# Mainboard_v4.net
KiCad netlist of a schematic drawn in EAGLE
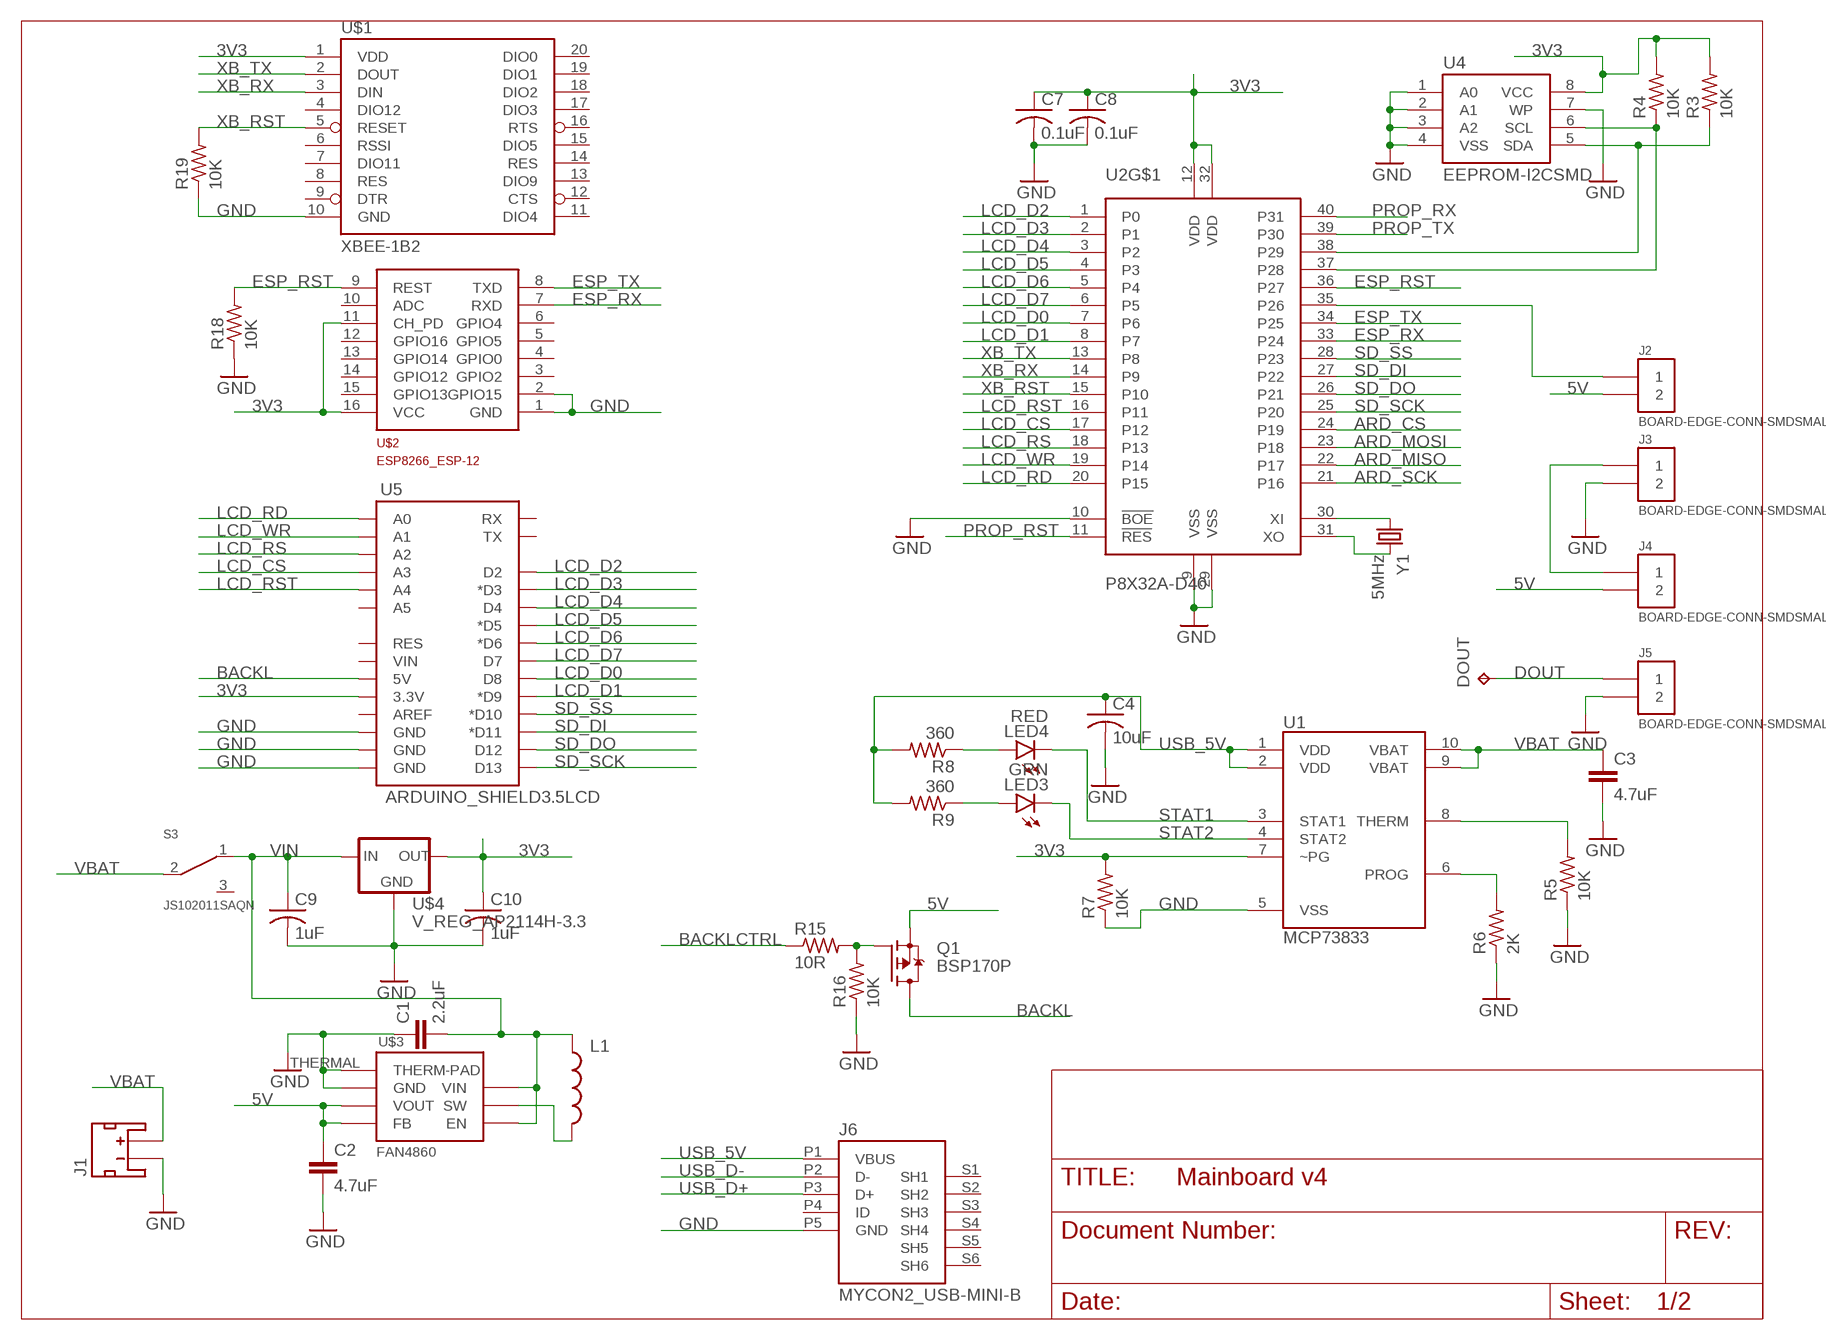
[diagram p0: schematic, sheet 1]
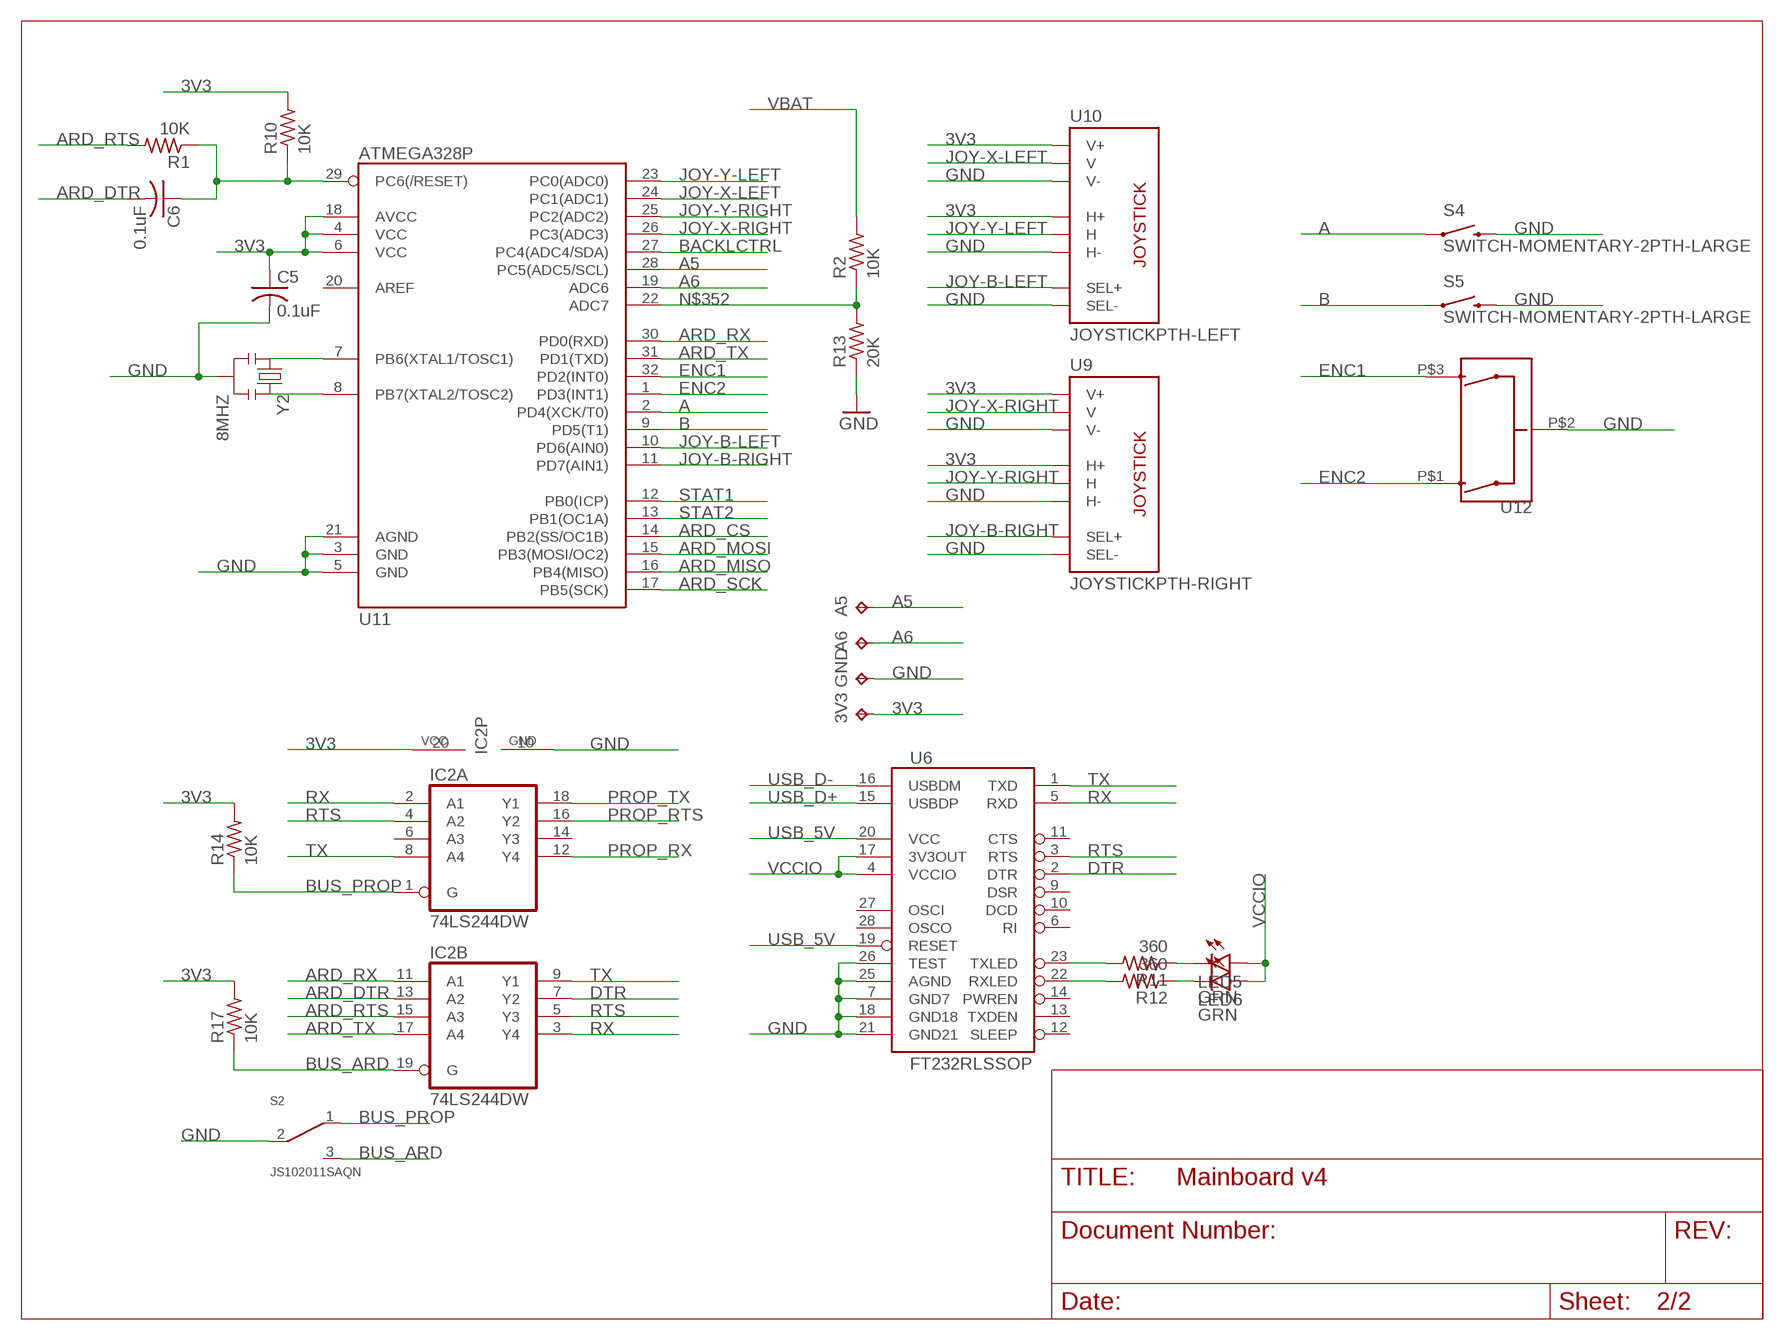
[diagram p1: schematic, sheet 2]

(export (version "E")
  (design (tool "Eeschema 10.0.6"))
  (components
    (comp (ref "C1")
      (value "2.2uF")
      (footprint "eagle-import:0402-CAP")
      (libsource (lib "eagle-import") (part "CAP0402-CAP"))
    )
    (comp (ref "C2")
      (value "4.7uF")
      (footprint "eagle-import:0603-CAP")
      (libsource (lib "eagle-import") (part "CAP0603-CAP"))
    )
    (comp (ref "C3")
      (value "4.7uF")
      (footprint "eagle-import:0603-CAP")
      (libsource (lib "eagle-import") (part "CAP0603-CAP"))
    )
    (comp (ref "C4")
      (value "10uF")
      (footprint "eagle-import:C1206K")
      (libsource (lib "eagle-import") (part "C-USC1206K"))
    )
    (comp (ref "C7")
      (value "0.1uF")
      (footprint "eagle-import:C0805")
      (libsource (lib "eagle-import") (part "C-USC0805"))
    )
    (comp (ref "C8")
      (value "0.1uF")
      (footprint "eagle-import:C0805")
      (libsource (lib "eagle-import") (part "C-USC0805"))
    )
    (comp (ref "C9")
      (value "1uF")
      (footprint "eagle-import:C1206K")
      (libsource (lib "eagle-import") (part "C-USC1206K"))
    )
    (comp (ref "C10")
      (value "1uF")
      (footprint "eagle-import:C1206K")
      (libsource (lib "eagle-import") (part "C-USC1206K"))
    )
    (comp (ref "DOUT")
      (value "TPPAD1-13")
      (footprint "eagle-import:P1-13")
      (libsource (lib "eagle-import") (part "TPPAD1-13"))
    )
    (comp (ref "J1")
      (value "JST_2MM_MALE")
      (footprint "eagle-import:JST-2-SMD")
      (libsource (lib "eagle-import") (part "JST_2MM_MALE"))
    )
    (comp (ref "J2")
      (value "BOARD-EDGE-CONN-SMDSMALL")
      (footprint "eagle-import:SMD-2-SMALL")
      (libsource (lib "eagle-import") (part "BOARD-EDGE-CONN-SMDSMALL"))
    )
    (comp (ref "J3")
      (value "BOARD-EDGE-CONN-SMDSMALL")
      (footprint "eagle-import:SMD-2-SMALL")
      (libsource (lib "eagle-import") (part "BOARD-EDGE-CONN-SMDSMALL"))
    )
    (comp (ref "J4")
      (value "BOARD-EDGE-CONN-SMDSMALL")
      (footprint "eagle-import:SMD-2-SMALL")
      (libsource (lib "eagle-import") (part "BOARD-EDGE-CONN-SMDSMALL"))
    )
    (comp (ref "J5")
      (value "BOARD-EDGE-CONN-SMDSMALL")
      (footprint "eagle-import:SMD-2-SMALL")
      (libsource (lib "eagle-import") (part "BOARD-EDGE-CONN-SMDSMALL"))
    )
    (comp (ref "J6")
      (value "MYCON2_USB-MINI-B")
      (footprint "eagle-import:CON2_USB_MICRO_B_AT")
      (libsource (lib "eagle-import") (part "MYCON2_USB-MINI-B"))
    )
    (comp (ref "L1")
      (value "INDUCTOR0805")
      (footprint "eagle-import:0805")
      (libsource (lib "eagle-import") (part "INDUCTOR0805"))
    )
    (comp (ref "LED3")
      (value "GRN")
      (footprint "eagle-import:LED-0603")
      (libsource (lib "eagle-import") (part "LED0603"))
    )
    (comp (ref "LED4")
      (value "RED")
      (footprint "eagle-import:LED-0603")
      (libsource (lib "eagle-import") (part "LED0603"))
    )
    (comp (ref "Q1")
      (value "BSP170P")
      (footprint "eagle-import:SOT223")
      (libsource (lib "eagle-import") (part "BSP170P"))
    )
    (comp (ref "R3")
      (value "10K")
      (footprint "eagle-import:R0603")
      (libsource (lib "eagle-import") (part "R-US_R0603"))
    )
    (comp (ref "R4")
      (value "10K")
      (footprint "eagle-import:R0603")
      (libsource (lib "eagle-import") (part "R-US_R0603"))
    )
    (comp (ref "R5")
      (value "10K")
      (footprint "eagle-import:R0603")
      (libsource (lib "eagle-import") (part "R-US_R0603"))
    )
    (comp (ref "R6")
      (value "2K")
      (footprint "eagle-import:R0603")
      (libsource (lib "eagle-import") (part "R-US_R0603"))
    )
    (comp (ref "R7")
      (value "10K")
      (footprint "eagle-import:R0603")
      (libsource (lib "eagle-import") (part "R-US_R0603"))
    )
    (comp (ref "R8")
      (value "360")
      (footprint "eagle-import:R0603")
      (libsource (lib "eagle-import") (part "R-US_R0603"))
    )
    (comp (ref "R9")
      (value "360")
      (footprint "eagle-import:R0603")
      (libsource (lib "eagle-import") (part "R-US_R0603"))
    )
    (comp (ref "R15")
      (value "10R")
      (footprint "eagle-import:R0603")
      (libsource (lib "eagle-import") (part "R-US_R0603"))
    )
    (comp (ref "R16")
      (value "10K")
      (footprint "eagle-import:R0603")
      (libsource (lib "eagle-import") (part "R-US_R0603"))
    )
    (comp (ref "R18")
      (value "10K")
      (footprint "eagle-import:R0603")
      (libsource (lib "eagle-import") (part "R-US_R0603"))
    )
    (comp (ref "R19")
      (value "10K")
      (footprint "eagle-import:R0603")
      (libsource (lib "eagle-import") (part "R-US_R0603"))
    )
    (comp (ref "S3")
      (value "JS102011SAQN")
      (footprint "eagle-import:SAQN")
      (libsource (lib "eagle-import") (part "JS102011SAQN"))
    )
    (comp (ref "U$1")
      (value "XBEE-1B2")
      (footprint "eagle-import:XBEE-SILK")
      (libsource (lib "eagle-import") (part "XBEE-1B2"))
    )
    (comp (ref "U$2")
      (value "ESP8266_ESP-12")
      (footprint "eagle-import:ESP8266-ESP12E")
      (libsource (lib "eagle-import") (part "ESP8266_ESP-12"))
    )
    (comp (ref "U$3")
      (value "FAN4860")
      (footprint "eagle-import:6-UMLP")
      (libsource (lib "eagle-import") (part "FAN4860"))
    )
    (comp (ref "U$4")
      (value "V_REG_AP2114H-3.3")
      (footprint "eagle-import:SOT223")
      (libsource (lib "eagle-import") (part "V_REG_MIC2920AP2114"))
    )
    (comp (ref "U1")
      (value "MCP73833")
      (footprint "eagle-import:MSOP-10")
      (libsource (lib "eagle-import") (part "MCP73833"))
    )
    (comp (ref "U2")
      (value "P8X32A-D40")
      (footprint "eagle-import:DIP-40")
      (libsource (lib "eagle-import") (part "P8X32A-D40"))
    )
    (comp (ref "U4")
      (value "EEPROM-I2CSMD")
      (footprint "eagle-import:SO08")
      (libsource (lib "eagle-import") (part "EEPROM-I2CSMD"))
    )
    (comp (ref "U5")
      (value "ARDUINO_SHIELD3.5LCD")
      (footprint "eagle-import:3.6TFT-LCD-SHIELD")
      (libsource (lib "eagle-import") (part "ARDUINO_SHIELD3.5LCD"))
    )
    (comp (ref "Y1")
      (value "5MHz")
      (footprint "eagle-import:CRYSTAL-SMD")
      (libsource (lib "eagle-import") (part "CRYSTAL-TH-11.5X5MM"))
    )
    (comp (ref "3V3")
      (value "TPPAD1-13")
      (footprint "eagle-import:P1-13")
      (libsource (lib "eagle-import") (part "TPPAD1-13"))
    )
    (comp (ref "A5")
      (value "TPPAD1-13")
      (footprint "eagle-import:P1-13")
      (libsource (lib "eagle-import") (part "TPPAD1-13"))
    )
    (comp (ref "A6")
      (value "TPPAD1-13")
      (footprint "eagle-import:P1-13")
      (libsource (lib "eagle-import") (part "TPPAD1-13"))
    )
    (comp (ref "C5")
      (value "0.1uF")
      (footprint "eagle-import:C0805")
      (libsource (lib "eagle-import") (part "C-USC0805"))
    )
    (comp (ref "C6")
      (value "0.1uF")
      (footprint "eagle-import:C0805")
      (libsource (lib "eagle-import") (part "C-USC0805"))
    )
    (comp (ref "GND")
      (value "TPPAD1-13")
      (footprint "eagle-import:P1-13")
      (libsource (lib "eagle-import") (part "TPPAD1-13"))
    )
    (comp (ref "IC2")
      (value "74LS244DW")
      (footprint "eagle-import:SO20W")
      (libsource (lib "eagle-import") (part "74244DWLS"))
    )
    (comp (ref "LED5")
      (value "GRN")
      (footprint "eagle-import:LED-0603")
      (libsource (lib "eagle-import") (part "LED0603"))
    )
    (comp (ref "LED6")
      (value "GRN")
      (footprint "eagle-import:LED-0603")
      (libsource (lib "eagle-import") (part "LED0603"))
    )
    (comp (ref "R1")
      (value "10K")
      (footprint "eagle-import:R0603")
      (libsource (lib "eagle-import") (part "R-US_R0603"))
    )
    (comp (ref "R2")
      (value "10K")
      (footprint "eagle-import:R0603")
      (libsource (lib "eagle-import") (part "R-US_R0603"))
    )
    (comp (ref "R10")
      (value "10K")
      (footprint "eagle-import:R0603")
      (libsource (lib "eagle-import") (part "R-US_R0603"))
    )
    (comp (ref "R11")
      (value "360")
      (footprint "eagle-import:R0603")
      (libsource (lib "eagle-import") (part "R-US_R0603"))
    )
    (comp (ref "R12")
      (value "360")
      (footprint "eagle-import:R0603")
      (libsource (lib "eagle-import") (part "R-US_R0603"))
    )
    (comp (ref "R13")
      (value "20K")
      (footprint "eagle-import:R0603")
      (libsource (lib "eagle-import") (part "R-US_R0603"))
    )
    (comp (ref "R14")
      (value "10K")
      (footprint "eagle-import:R0603")
      (libsource (lib "eagle-import") (part "R-US_R0603"))
    )
    (comp (ref "R17")
      (value "10K")
      (footprint "eagle-import:R0603")
      (libsource (lib "eagle-import") (part "R-US_R0603"))
    )
    (comp (ref "S2")
      (value "JS102011SAQN")
      (footprint "eagle-import:SAQN")
      (libsource (lib "eagle-import") (part "JS102011SAQN"))
    )
    (comp (ref "S4")
      (value "SWITCH-MOMENTARY-2PTH-LARGE")
      (footprint "eagle-import:TACTILE-PTH-LARGE")
      (libsource (lib "eagle-import") (part "SWITCH-MOMENTARY-2PTH-LARGE"))
    )
    (comp (ref "S5")
      (value "SWITCH-MOMENTARY-2PTH-LARGE")
      (footprint "eagle-import:TACTILE-PTH-LARGE")
      (libsource (lib "eagle-import") (part "SWITCH-MOMENTARY-2PTH-LARGE"))
    )
    (comp (ref "U6")
      (value "FT232RLSSOP")
      (footprint "eagle-import:SSOP28DB")
      (libsource (lib "eagle-import") (part "FT232RLSSOP"))
    )
    (comp (ref "U9")
      (value "JOYSTICKPTH-RIGHT")
      (footprint "eagle-import:JOYSTICK")
      (libsource (lib "eagle-import") (part "JOYSTICKPTH"))
    )
    (comp (ref "U10")
      (value "JOYSTICKPTH-LEFT")
      (footprint "eagle-import:JOYSTICK")
      (libsource (lib "eagle-import") (part "JOYSTICKPTH"))
    )
    (comp (ref "U11")
      (value "ATMEGA328P")
      (footprint "eagle-import:TQFP32-08")
      (libsource (lib "eagle-import") (part "ATMEGA328_SMT"))
    )
    (comp (ref "U12")
      (value "ENCODER-QUADRATURE")
      (footprint "eagle-import:ENCODER-12MM-VERT-SQ")
      (libsource (lib "eagle-import") (part "ENCODER-QUADRATURE"))
    )
    (comp (ref "Y2")
      (value "8MHZ")
      (footprint "eagle-import:RESONATOR-AWSCR-CV")
      (libsource (lib "eagle-import") (part "RESONATORAWSCR"))
    )
  )
  (nets
    (net (code "1") (name "3V3") (class "Default")
      (node (ref "3V3") (pin "TP") (pinfunction "TP_TP") (pintype "input"))
      (node (ref "C10") (pin "1") (pinfunction "1_1") (pintype "passive"))
      (node (ref "C5") (pin "1") (pinfunction "1_1") (pintype "passive"))
      (node (ref "C7") (pin "1") (pinfunction "1_1") (pintype "passive"))
      (node (ref "C8") (pin "1") (pinfunction "1_1") (pintype "passive"))
      (node (ref "IC2") (pin "20") (pinfunction "VCC_20") (pintype "power_in"))
      (node (ref "R10") (pin "2") (pinfunction "2_2") (pintype "passive"))
      (node (ref "R14") (pin "2") (pinfunction "2_2") (pintype "passive"))
      (node (ref "R17") (pin "2") (pinfunction "2_2") (pintype "passive"))
      (node (ref "R3") (pin "2") (pinfunction "2_2") (pintype "passive"))
      (node (ref "R4") (pin "2") (pinfunction "2_2") (pintype "passive"))
      (node (ref "R7") (pin "2") (pinfunction "2_2") (pintype "passive"))
      (node (ref "U$1") (pin "1") (pinfunction "VDD_1") (pintype "power_in"))
      (node (ref "U$2") (pin "11") (pinfunction "CH_PD_11") (pintype "bidirectional"))
      (node (ref "U$2") (pin "16") (pinfunction "VCC_16") (pintype "bidirectional"))
      (node (ref "U$4") (pin "2") (pinfunction "OUT_2") (pintype "output"))
      (node (ref "U1") (pin "7") (pinfunction "~{PG}_7") (pintype "bidirectional"))
      (node (ref "U10") (pin "H1") (pinfunction "H+_H1") (pintype "bidirectional"))
      (node (ref "U10") (pin "V1") (pinfunction "V+_V1") (pintype "bidirectional"))
      (node (ref "U11") (pin "18") (pinfunction "AVCC_18") (pintype "bidirectional"))
      (node (ref "U11") (pin "4") (pinfunction "VCC_4") (pintype "bidirectional"))
      (node (ref "U11") (pin "6") (pinfunction "VCC_6") (pintype "bidirectional"))
      (node (ref "U2") (pin "12") (pinfunction "VDD_12") (pintype "input"))
      (node (ref "U2") (pin "32") (pinfunction "VDD_32") (pintype "input"))
      (node (ref "U4") (pin "8") (pinfunction "VCC_8") (pintype "power_in"))
      (node (ref "U5") (pin "3.3V") (pinfunction "3.3V_3.3V") (pintype "bidirectional"))
      (node (ref "U9") (pin "H1") (pinfunction "H+_H1") (pintype "bidirectional"))
      (node (ref "U9") (pin "V1") (pinfunction "V+_V1") (pintype "bidirectional"))
    )
    (net (code "2") (name "5V") (class "Default")
      (node (ref "C2") (pin "1") (pinfunction "1_1") (pintype "passive"))
      (node (ref "J2") (pin "P$2") (pinfunction "2_P$2") (pintype "bidirectional"))
      (node (ref "J4") (pin "P$2") (pinfunction "2_P$2") (pintype "bidirectional"))
      (node (ref "Q1") (pin "3") (pinfunction "S_3") (pintype "passive"))
      (node (ref "U$3") (pin "P$2") (pinfunction "VOUT_P$2") (pintype "bidirectional"))
      (node (ref "U$3") (pin "P$3") (pinfunction "FB_P$3") (pintype "bidirectional"))
    )
    (net (code "3") (name "A") (class "Default")
      (node (ref "S4") (pin "P$1") (pinfunction "1_P$1") (pintype "passive"))
      (node (ref "U11") (pin "2") (pinfunction "PD4(XCK/T0)_2") (pintype "bidirectional"))
    )
    (net (code "4") (name "A5") (class "Default")
      (node (ref "A5") (pin "TP") (pinfunction "TP_TP") (pintype "input"))
      (node (ref "U11") (pin "28") (pinfunction "PC5(ADC5/SCL)_28") (pintype "bidirectional"))
    )
    (net (code "5") (name "A6") (class "Default")
      (node (ref "A6") (pin "TP") (pinfunction "TP_TP") (pintype "input"))
      (node (ref "U11") (pin "19") (pinfunction "ADC6_19") (pintype "bidirectional"))
    )
    (net (code "6") (name "ARD_CS") (class "Default")
      (node (ref "U11") (pin "14") (pinfunction "PB2(SS/OC1B)_14") (pintype "bidirectional"))
      (node (ref "U2") (pin "24") (pinfunction "P19_24") (pintype "bidirectional"))
    )
    (net (code "7") (name "ARD_DTR") (class "Default")
      (node (ref "C6") (pin "2") (pinfunction "2_2") (pintype "passive"))
      (node (ref "IC2") (pin "13") (pinfunction "A2_13") (pintype "input"))
    )
    (net (code "8") (name "ARD_MISO") (class "Default")
      (node (ref "U11") (pin "16") (pinfunction "PB4(MISO)_16") (pintype "bidirectional"))
      (node (ref "U2") (pin "22") (pinfunction "P17_22") (pintype "bidirectional"))
    )
    (net (code "9") (name "ARD_MOSI") (class "Default")
      (node (ref "U11") (pin "15") (pinfunction "PB3(MOSI/OC2)_15") (pintype "bidirectional"))
      (node (ref "U2") (pin "23") (pinfunction "P18_23") (pintype "bidirectional"))
    )
    (net (code "10") (name "ARD_RTS") (class "Default")
      (node (ref "IC2") (pin "15") (pinfunction "A3_15") (pintype "input"))
      (node (ref "R1") (pin "2") (pinfunction "2_2") (pintype "passive"))
    )
    (net (code "11") (name "ARD_RX") (class "Default")
      (node (ref "IC2") (pin "11") (pinfunction "A1_11") (pintype "input"))
      (node (ref "U11") (pin "30") (pinfunction "PD0(RXD)_30") (pintype "bidirectional"))
    )
    (net (code "12") (name "ARD_SCK") (class "Default")
      (node (ref "U11") (pin "17") (pinfunction "PB5(SCK)_17") (pintype "bidirectional"))
      (node (ref "U2") (pin "21") (pinfunction "P16_21") (pintype "bidirectional"))
    )
    (net (code "13") (name "ARD_TX") (class "Default")
      (node (ref "IC2") (pin "17") (pinfunction "A4_17") (pintype "input"))
      (node (ref "U11") (pin "31") (pinfunction "PD1(TXD)_31") (pintype "bidirectional"))
    )
    (net (code "14") (name "B") (class "Default")
      (node (ref "S5") (pin "P$1") (pinfunction "1_P$1") (pintype "passive"))
      (node (ref "U11") (pin "9") (pinfunction "PD5(T1)_9") (pintype "bidirectional"))
    )
    (net (code "15") (name "BACKL") (class "Default")
      (node (ref "Q1") (pin "2") (pinfunction "D_2") (pintype "passive"))
      (node (ref "Q1") (pin "4") (pinfunction "D_4") (pintype "passive"))
      (node (ref "U5") (pin "5V") (pinfunction "5V_5V") (pintype "bidirectional"))
    )
    (net (code "16") (name "BACKLCTRL") (class "Default")
      (node (ref "R15") (pin "1") (pinfunction "1_1") (pintype "passive"))
      (node (ref "U11") (pin "27") (pinfunction "PC4(ADC4/SDA)_27") (pintype "bidirectional"))
    )
    (net (code "17") (name "BUS_ARD") (class "Default")
      (node (ref "IC2") (pin "19") (pinfunction "G_19") (pintype "input"))
      (node (ref "R17") (pin "1") (pinfunction "1_1") (pintype "passive"))
      (node (ref "S2") (pin "3") (pinfunction "P3_3") (pintype "bidirectional"))
    )
    (net (code "18") (name "BUS_PROP") (class "Default")
      (node (ref "IC2") (pin "1") (pinfunction "G_1") (pintype "input"))
      (node (ref "R14") (pin "1") (pinfunction "1_1") (pintype "passive"))
      (node (ref "S2") (pin "1") (pinfunction "P1_1") (pintype "bidirectional"))
    )
    (net (code "19") (name "DOUT") (class "Default")
      (node (ref "DOUT") (pin "TP") (pinfunction "TP_TP") (pintype "input"))
      (node (ref "J5") (pin "P$1") (pinfunction "1_P$1") (pintype "bidirectional"))
    )
    (net (code "20") (name "DTR") (class "Default")
      (node (ref "IC2") (pin "7") (pinfunction "Y2_7") (pintype "tri_state"))
      (node (ref "U6") (pin "2") (pinfunction "DTR_2") (pintype "output"))
    )
    (net (code "21") (name "ENC1") (class "Default")
      (node (ref "U11") (pin "32") (pinfunction "PD2(INT0)_32") (pintype "bidirectional"))
      (node (ref "U12") (pin "P$3") (pinfunction "B_P$3") (pintype "bidirectional"))
    )
    (net (code "22") (name "ENC2") (class "Default")
      (node (ref "U11") (pin "1") (pinfunction "PD3(INT1)_1") (pintype "bidirectional"))
      (node (ref "U12") (pin "P$1") (pinfunction "A_P$1") (pintype "bidirectional"))
    )
    (net (code "23") (name "ESP_RST") (class "Default")
      (node (ref "R18") (pin "2") (pinfunction "2_2") (pintype "passive"))
      (node (ref "U$2") (pin "9") (pinfunction "REST_9") (pintype "bidirectional"))
      (node (ref "U2") (pin "36") (pinfunction "P27_36") (pintype "bidirectional"))
    )
    (net (code "24") (name "ESP_RX") (class "Default")
      (node (ref "U$2") (pin "7") (pinfunction "RXD_7") (pintype "bidirectional"))
      (node (ref "U2") (pin "33") (pinfunction "P24_33") (pintype "bidirectional"))
    )
    (net (code "25") (name "ESP_TX") (class "Default")
      (node (ref "U$2") (pin "8") (pinfunction "TXD_8") (pintype "bidirectional"))
      (node (ref "U2") (pin "34") (pinfunction "P25_34") (pintype "bidirectional"))
    )
    (net (code "26") (name "GND") (class "Default")
      (node (ref "C1") (pin "1") (pinfunction "1_1") (pintype "passive"))
      (node (ref "C10") (pin "2") (pinfunction "2_2") (pintype "passive"))
      (node (ref "C2") (pin "2") (pinfunction "2_2") (pintype "passive"))
      (node (ref "C3") (pin "2") (pinfunction "2_2") (pintype "passive"))
      (node (ref "C4") (pin "2") (pinfunction "2_2") (pintype "passive"))
      (node (ref "C5") (pin "2") (pinfunction "2_2") (pintype "passive"))
      (node (ref "C7") (pin "2") (pinfunction "2_2") (pintype "passive"))
      (node (ref "C8") (pin "2") (pinfunction "2_2") (pintype "passive"))
      (node (ref "C9") (pin "2") (pinfunction "2_2") (pintype "passive"))
      (node (ref "GND") (pin "TP") (pinfunction "TP_TP") (pintype "input"))
      (node (ref "IC2") (pin "10") (pinfunction "GND_10") (pintype "power_in"))
      (node (ref "J1") (pin "1") (pinfunction "-_1") (pintype "bidirectional"))
      (node (ref "J3") (pin "P$2") (pinfunction "2_P$2") (pintype "bidirectional"))
      (node (ref "J5") (pin "P$2") (pinfunction "2_P$2") (pintype "bidirectional"))
      (node (ref "J6") (pin "P5") (pinfunction "GND_P5") (pintype "passive"))
      (node (ref "R13") (pin "1") (pinfunction "1_1") (pintype "passive"))
      (node (ref "R16") (pin "1") (pinfunction "1_1") (pintype "passive"))
      (node (ref "R18") (pin "1") (pinfunction "1_1") (pintype "passive"))
      (node (ref "R19") (pin "1") (pinfunction "1_1") (pintype "passive"))
      (node (ref "R5") (pin "1") (pinfunction "1_1") (pintype "passive"))
      (node (ref "R6") (pin "1") (pinfunction "1_1") (pintype "passive"))
      (node (ref "R7") (pin "1") (pinfunction "1_1") (pintype "passive"))
      (node (ref "S2") (pin "2") (pinfunction "P2_2") (pintype "bidirectional"))
      (node (ref "S4") (pin "P$2") (pinfunction "2_P$2") (pintype "passive"))
      (node (ref "S5") (pin "P$2") (pinfunction "2_P$2") (pintype "passive"))
      (node (ref "U$1") (pin "10") (pinfunction "GND_10") (pintype "power_in"))
      (node (ref "U$2") (pin "1") (pinfunction "GND_1") (pintype "bidirectional"))
      (node (ref "U$2") (pin "2") (pinfunction "GPIO15_2") (pintype "bidirectional"))
      (node (ref "U$3") (pin "P$1") (pinfunction "GND_P$1") (pintype "bidirectional"))
      (node (ref "U$3") (pin "THERMAL") (pinfunction "THERM-PAD_THERMAL") (pintype "bidirectional"))
      (node (ref "U$4") (pin "1") (pinfunction "GND_1") (pintype "input"))
      (node (ref "U1") (pin "5") (pinfunction "VSS_5") (pintype "bidirectional"))
      (node (ref "U10") (pin "B2A") (pinfunction "SEL-_B2A") (pintype "bidirectional"))
      (node (ref "U10") (pin "H3") (pinfunction "H-_H3") (pintype "bidirectional"))
      (node (ref "U10") (pin "V3") (pinfunction "V-_V3") (pintype "bidirectional"))
      (node (ref "U11") (pin "21") (pinfunction "AGND_21") (pintype "bidirectional"))
      (node (ref "U11") (pin "3") (pinfunction "GND_3") (pintype "bidirectional"))
      (node (ref "U11") (pin "5") (pinfunction "GND_5") (pintype "bidirectional"))
      (node (ref "U12") (pin "P$2") (pinfunction "C_P$2") (pintype "bidirectional"))
      (node (ref "U2") (pin "10") (pinfunction "~{BOE}_10") (pintype "input"))
      (node (ref "U2") (pin "29") (pinfunction "VSS_29") (pintype "input"))
      (node (ref "U2") (pin "9") (pinfunction "VSS_9") (pintype "input"))
      (node (ref "U4") (pin "1") (pinfunction "A0_1") (pintype "bidirectional"))
      (node (ref "U4") (pin "2") (pinfunction "A1_2") (pintype "bidirectional"))
      (node (ref "U4") (pin "3") (pinfunction "A2_3") (pintype "bidirectional"))
      (node (ref "U4") (pin "4") (pinfunction "VSS_4") (pintype "power_in"))
      (node (ref "U4") (pin "7") (pinfunction "WP_7") (pintype "bidirectional"))
      (node (ref "U5") (pin "GND@0") (pinfunction "GND_GND@0") (pintype "bidirectional"))
      (node (ref "U5") (pin "GND@1") (pinfunction "GND_GND@1") (pintype "bidirectional"))
      (node (ref "U5") (pin "GND@2") (pinfunction "GND_GND@2") (pintype "bidirectional"))
      (node (ref "U6") (pin "18") (pinfunction "GND18_18") (pintype "power_in"))
      (node (ref "U6") (pin "21") (pinfunction "GND21_21") (pintype "power_in"))
      (node (ref "U6") (pin "25") (pinfunction "AGND_25") (pintype "power_in"))
      (node (ref "U6") (pin "26") (pinfunction "TEST_26") (pintype "input"))
      (node (ref "U6") (pin "7") (pinfunction "GND7_7") (pintype "power_in"))
      (node (ref "U9") (pin "B2A") (pinfunction "SEL-_B2A") (pintype "bidirectional"))
      (node (ref "U9") (pin "H3") (pinfunction "H-_H3") (pintype "bidirectional"))
      (node (ref "U9") (pin "V3") (pinfunction "V-_V3") (pintype "bidirectional"))
      (node (ref "Y2") (pin "P$2") (pinfunction "2_P$2") (pintype "passive"))
    )
    (net (code "27") (name "JOY-B-LEFT") (class "Default")
      (node (ref "U10") (pin "B1A") (pinfunction "SEL+_B1A") (pintype "bidirectional"))
      (node (ref "U11") (pin "10") (pinfunction "PD6(AIN0)_10") (pintype "bidirectional"))
    )
    (net (code "28") (name "JOY-B-RIGHT") (class "Default")
      (node (ref "U11") (pin "11") (pinfunction "PD7(AIN1)_11") (pintype "bidirectional"))
      (node (ref "U9") (pin "B1A") (pinfunction "SEL+_B1A") (pintype "bidirectional"))
    )
    (net (code "29") (name "JOY-X-LEFT") (class "Default")
      (node (ref "U10") (pin "V2") (pinfunction "V_V2") (pintype "bidirectional"))
      (node (ref "U11") (pin "24") (pinfunction "PC1(ADC1)_24") (pintype "bidirectional"))
    )
    (net (code "30") (name "JOY-X-RIGHT") (class "Default")
      (node (ref "U11") (pin "26") (pinfunction "PC3(ADC3)_26") (pintype "bidirectional"))
      (node (ref "U9") (pin "V2") (pinfunction "V_V2") (pintype "bidirectional"))
    )
    (net (code "31") (name "JOY-Y-LEFT") (class "Default")
      (node (ref "U10") (pin "H2") (pinfunction "H_H2") (pintype "bidirectional"))
      (node (ref "U11") (pin "23") (pinfunction "PC0(ADC0)_23") (pintype "bidirectional"))
    )
    (net (code "32") (name "JOY-Y-RIGHT") (class "Default")
      (node (ref "U11") (pin "25") (pinfunction "PC2(ADC2)_25") (pintype "bidirectional"))
      (node (ref "U9") (pin "H2") (pinfunction "H_H2") (pintype "bidirectional"))
    )
    (net (code "33") (name "LCD_CS") (class "Default")
      (node (ref "U2") (pin "17") (pinfunction "P12_17") (pintype "bidirectional"))
      (node (ref "U5") (pin "A3") (pinfunction "A3_A3") (pintype "bidirectional"))
    )
    (net (code "34") (name "LCD_D0") (class "Default")
      (node (ref "U2") (pin "7") (pinfunction "P6_7") (pintype "bidirectional"))
      (node (ref "U5") (pin "D8") (pinfunction "D8_D8") (pintype "bidirectional"))
    )
    (net (code "35") (name "LCD_D1") (class "Default")
      (node (ref "U2") (pin "8") (pinfunction "P7_8") (pintype "bidirectional"))
      (node (ref "U5") (pin "D9") (pinfunction "*D9_D9") (pintype "bidirectional"))
    )
    (net (code "36") (name "LCD_D2") (class "Default")
      (node (ref "U2") (pin "1") (pinfunction "P0_1") (pintype "bidirectional"))
      (node (ref "U5") (pin "D2") (pinfunction "D2_D2") (pintype "bidirectional"))
    )
    (net (code "37") (name "LCD_D3") (class "Default")
      (node (ref "U2") (pin "2") (pinfunction "P1_2") (pintype "bidirectional"))
      (node (ref "U5") (pin "D3") (pinfunction "*D3_D3") (pintype "bidirectional"))
    )
    (net (code "38") (name "LCD_D4") (class "Default")
      (node (ref "U2") (pin "3") (pinfunction "P2_3") (pintype "bidirectional"))
      (node (ref "U5") (pin "D4") (pinfunction "D4_D4") (pintype "bidirectional"))
    )
    (net (code "39") (name "LCD_D5") (class "Default")
      (node (ref "U2") (pin "4") (pinfunction "P3_4") (pintype "bidirectional"))
      (node (ref "U5") (pin "D5") (pinfunction "*D5_D5") (pintype "bidirectional"))
    )
    (net (code "40") (name "LCD_D6") (class "Default")
      (node (ref "U2") (pin "5") (pinfunction "P4_5") (pintype "bidirectional"))
      (node (ref "U5") (pin "D6") (pinfunction "*D6_D6") (pintype "bidirectional"))
    )
    (net (code "41") (name "LCD_D7") (class "Default")
      (node (ref "U2") (pin "6") (pinfunction "P5_6") (pintype "bidirectional"))
      (node (ref "U5") (pin "D7") (pinfunction "D7_D7") (pintype "bidirectional"))
    )
    (net (code "42") (name "LCD_RD") (class "Default")
      (node (ref "U2") (pin "20") (pinfunction "P15_20") (pintype "bidirectional"))
      (node (ref "U5") (pin "A0") (pinfunction "A0_A0") (pintype "bidirectional"))
    )
    (net (code "43") (name "LCD_RS") (class "Default")
      (node (ref "U2") (pin "18") (pinfunction "P13_18") (pintype "bidirectional"))
      (node (ref "U5") (pin "A2") (pinfunction "A2_A2") (pintype "bidirectional"))
    )
    (net (code "44") (name "LCD_RST") (class "Default")
      (node (ref "U2") (pin "16") (pinfunction "P11_16") (pintype "bidirectional"))
      (node (ref "U5") (pin "A4") (pinfunction "A4_A4") (pintype "bidirectional"))
    )
    (net (code "45") (name "LCD_WR") (class "Default")
      (node (ref "U2") (pin "19") (pinfunction "P14_19") (pintype "bidirectional"))
      (node (ref "U5") (pin "A1") (pinfunction "A1_A1") (pintype "bidirectional"))
    )
    (net (code "46") (name "N$352") (class "Default")
      (node (ref "R13") (pin "2") (pinfunction "2_2") (pintype "passive"))
      (node (ref "R2") (pin "1") (pinfunction "1_1") (pintype "passive"))
      (node (ref "U11") (pin "22") (pinfunction "ADC7_22") (pintype "bidirectional"))
    )
    (net (code "47") (name "Net-(J2-1)") (class "Default")
      (node (ref "J2") (pin "P$1") (pinfunction "1_P$1") (pintype "bidirectional"))
      (node (ref "U2") (pin "35") (pinfunction "P26_35") (pintype "bidirectional"))
    )
    (net (code "48") (name "Net-(J3-1)") (class "Default")
      (node (ref "J3") (pin "P$1") (pinfunction "1_P$1") (pintype "bidirectional"))
      (node (ref "J4") (pin "P$1") (pinfunction "1_P$1") (pintype "bidirectional"))
    )
    (net (code "49") (name "Net-(LED3-PadA)") (class "Default")
      (node (ref "LED3") (pin "A") (pinfunction "A_A") (pintype "passive"))
      (node (ref "R9") (pin "1") (pinfunction "1_1") (pintype "passive"))
    )
    (net (code "50") (name "Net-(LED4-PadA)") (class "Default")
      (node (ref "LED4") (pin "A") (pinfunction "A_A") (pintype "passive"))
      (node (ref "R8") (pin "1") (pinfunction "1_1") (pintype "passive"))
    )
    (net (code "51") (name "Net-(LED5-PadC)") (class "Default")
      (node (ref "LED5") (pin "C") (pinfunction "C_C") (pintype "passive"))
      (node (ref "R11") (pin "1") (pinfunction "1_1") (pintype "passive"))
    )
    (net (code "52") (name "Net-(LED6-PadC)") (class "Default")
      (node (ref "LED6") (pin "C") (pinfunction "C_C") (pintype "passive"))
      (node (ref "R12") (pin "1") (pinfunction "1_1") (pintype "passive"))
    )
    (net (code "53") (name "Net-(Q1-G)") (class "Default")
      (node (ref "Q1") (pin "1") (pinfunction "G_1") (pintype "passive"))
      (node (ref "R15") (pin "2") (pinfunction "2_2") (pintype "passive"))
      (node (ref "R16") (pin "2") (pinfunction "2_2") (pintype "passive"))
    )
    (net (code "54") (name "Net-(U$3-SW)") (class "Default")
      (node (ref "L1") (pin "2") (pinfunction "2_2") (pintype "passive"))
      (node (ref "U$3") (pin "P$5") (pinfunction "SW_P$5") (pintype "bidirectional"))
    )
    (net (code "55") (name "Net-(U1-PROG)") (class "Default")
      (node (ref "R6") (pin "2") (pinfunction "2_2") (pintype "passive"))
      (node (ref "U1") (pin "6") (pinfunction "PROG_6") (pintype "bidirectional"))
    )
    (net (code "56") (name "Net-(U1-THERM)") (class "Default")
      (node (ref "R5") (pin "2") (pinfunction "2_2") (pintype "passive"))
      (node (ref "U1") (pin "8") (pinfunction "THERM_8") (pintype "bidirectional"))
    )
    (net (code "57") (name "Net-(U2A-P28)") (class "Default")
      (node (ref "R4") (pin "1") (pinfunction "1_1") (pintype "passive"))
      (node (ref "U2") (pin "37") (pinfunction "P28_37") (pintype "bidirectional"))
      (node (ref "U4") (pin "6") (pinfunction "SCL_6") (pintype "bidirectional"))
    )
    (net (code "58") (name "Net-(U2A-P29)") (class "Default")
      (node (ref "R3") (pin "1") (pinfunction "1_1") (pintype "passive"))
      (node (ref "U2") (pin "38") (pinfunction "P29_38") (pintype "bidirectional"))
      (node (ref "U4") (pin "5") (pinfunction "SDA_5") (pintype "bidirectional"))
    )
    (net (code "59") (name "Net-(U2A-XI)") (class "Default")
      (node (ref "U2") (pin "30") (pinfunction "XI_30") (pintype "input"))
      (node (ref "Y1") (pin "P$1") (pinfunction "1_P$1") (pintype "passive"))
    )
    (net (code "60") (name "Net-(U2A-XO)") (class "Default")
      (node (ref "U2") (pin "31") (pinfunction "XO_31") (pintype "output"))
      (node (ref "Y1") (pin "P$2") (pinfunction "2_P$2") (pintype "passive"))
    )
    (net (code "61") (name "Net-(U6-RXLED)") (class "Default")
      (node (ref "R12") (pin "2") (pinfunction "2_2") (pintype "passive"))
      (node (ref "U6") (pin "22") (pinfunction "RXLED_22") (pintype "input"))
    )
    (net (code "62") (name "Net-(U6-TXLED)") (class "Default")
      (node (ref "R11") (pin "2") (pinfunction "2_2") (pintype "passive"))
      (node (ref "U6") (pin "23") (pinfunction "TXLED_23") (pintype "input"))
    )
    (net (code "63") (name "Net-(U11-PB6(XTAL1{slash}TOSC1))") (class "Default")
      (node (ref "U11") (pin "7") (pinfunction "PB6(XTAL1/TOSC1)_7") (pintype "bidirectional"))
      (node (ref "Y2") (pin "P$1") (pinfunction "1_P$1") (pintype "passive"))
    )
    (net (code "64") (name "Net-(U11-PB7(XTAL2{slash}TOSC2))") (class "Default")
      (node (ref "U11") (pin "8") (pinfunction "PB7(XTAL2/TOSC2)_8") (pintype "bidirectional"))
      (node (ref "Y2") (pin "P$3") (pinfunction "3_P$3") (pintype "passive"))
    )
    (net (code "65") (name "Net-(U11-PC6({slash}RESET))") (class "Default")
      (node (ref "C6") (pin "1") (pinfunction "1_1") (pintype "passive"))
      (node (ref "R1") (pin "1") (pinfunction "1_1") (pintype "passive"))
      (node (ref "R10") (pin "1") (pinfunction "1_1") (pintype "passive"))
      (node (ref "U11") (pin "29") (pinfunction "PC6(/RESET)_29") (pintype "bidirectional"))
    )
    (net (code "66") (name "PROP_RST") (class "Default")
      (node (ref "U2") (pin "11") (pinfunction "~{RES}_11") (pintype "bidirectional"))
    )
    (net (code "67") (name "PROP_RTS") (class "Default")
      (node (ref "IC2") (pin "16") (pinfunction "Y2_16") (pintype "tri_state"))
    )
    (net (code "68") (name "PROP_RX") (class "Default")
      (node (ref "IC2") (pin "12") (pinfunction "Y4_12") (pintype "tri_state"))
      (node (ref "U2") (pin "40") (pinfunction "P31_40") (pintype "bidirectional"))
    )
    (net (code "69") (name "PROP_TX") (class "Default")
      (node (ref "IC2") (pin "18") (pinfunction "Y1_18") (pintype "tri_state"))
      (node (ref "U2") (pin "39") (pinfunction "P30_39") (pintype "bidirectional"))
    )
    (net (code "70") (name "RTS") (class "Default")
      (node (ref "IC2") (pin "4") (pinfunction "A2_4") (pintype "input"))
      (node (ref "IC2") (pin "5") (pinfunction "Y3_5") (pintype "tri_state"))
      (node (ref "U6") (pin "3") (pinfunction "RTS_3") (pintype "output"))
    )
    (net (code "71") (name "RX") (class "Default")
      (node (ref "IC2") (pin "2") (pinfunction "A1_2") (pintype "input"))
      (node (ref "IC2") (pin "3") (pinfunction "Y4_3") (pintype "tri_state"))
      (node (ref "U6") (pin "5") (pinfunction "RXD_5") (pintype "input"))
    )
    (net (code "72") (name "SD_DI") (class "Default")
      (node (ref "U2") (pin "27") (pinfunction "P22_27") (pintype "bidirectional"))
      (node (ref "U5") (pin "D11") (pinfunction "*D11_D11") (pintype "bidirectional"))
    )
    (net (code "73") (name "SD_DO") (class "Default")
      (node (ref "U2") (pin "26") (pinfunction "P21_26") (pintype "bidirectional"))
      (node (ref "U5") (pin "D12") (pinfunction "D12_D12") (pintype "bidirectional"))
    )
    (net (code "74") (name "SD_SCK") (class "Default")
      (node (ref "U2") (pin "25") (pinfunction "P20_25") (pintype "bidirectional"))
      (node (ref "U5") (pin "D13") (pinfunction "D13_D13") (pintype "bidirectional"))
    )
    (net (code "75") (name "SD_SS") (class "Default")
      (node (ref "U2") (pin "28") (pinfunction "P23_28") (pintype "bidirectional"))
      (node (ref "U5") (pin "D10") (pinfunction "*D10_D10") (pintype "bidirectional"))
    )
    (net (code "76") (name "STAT1") (class "Default")
      (node (ref "LED4") (pin "C") (pinfunction "C_C") (pintype "passive"))
      (node (ref "U1") (pin "3") (pinfunction "STAT1_3") (pintype "bidirectional"))
      (node (ref "U11") (pin "12") (pinfunction "PB0(ICP)_12") (pintype "bidirectional"))
    )
    (net (code "77") (name "STAT2") (class "Default")
      (node (ref "LED3") (pin "C") (pinfunction "C_C") (pintype "passive"))
      (node (ref "U1") (pin "4") (pinfunction "STAT2_4") (pintype "bidirectional"))
      (node (ref "U11") (pin "13") (pinfunction "PB1(OC1A)_13") (pintype "bidirectional"))
    )
    (net (code "78") (name "TX") (class "Default")
      (node (ref "IC2") (pin "8") (pinfunction "A4_8") (pintype "input"))
      (node (ref "IC2") (pin "9") (pinfunction "Y1_9") (pintype "tri_state"))
      (node (ref "U6") (pin "1") (pinfunction "TXD_1") (pintype "output"))
    )
    (net (code "79") (name "USB_5V") (class "Default")
      (node (ref "C4") (pin "1") (pinfunction "1_1") (pintype "passive"))
      (node (ref "J6") (pin "P1") (pinfunction "VBUS_P1") (pintype "power_in"))
      (node (ref "R8") (pin "2") (pinfunction "2_2") (pintype "passive"))
      (node (ref "R9") (pin "2") (pinfunction "2_2") (pintype "passive"))
      (node (ref "U1") (pin "1") (pinfunction "VDD_1") (pintype "bidirectional"))
      (node (ref "U1") (pin "2") (pinfunction "VDD_2") (pintype "bidirectional"))
      (node (ref "U6") (pin "19") (pinfunction "RESET_19") (pintype "input"))
      (node (ref "U6") (pin "20") (pinfunction "VCC_20") (pintype "power_in"))
    )
    (net (code "80") (name "USB_D+") (class "Default")
      (node (ref "J6") (pin "P3") (pinfunction "D+_P3") (pintype "bidirectional"))
      (node (ref "U6") (pin "15") (pinfunction "USBDP_15") (pintype "bidirectional"))
    )
    (net (code "81") (name "USB_D-") (class "Default")
      (node (ref "J6") (pin "P2") (pinfunction "D-_P2") (pintype "bidirectional"))
      (node (ref "U6") (pin "16") (pinfunction "USBDM_16") (pintype "bidirectional"))
    )
    (net (code "82") (name "VBAT") (class "Default")
      (node (ref "C3") (pin "1") (pinfunction "1_1") (pintype "passive"))
      (node (ref "J1") (pin "2") (pinfunction "+_2") (pintype "bidirectional"))
      (node (ref "R2") (pin "2") (pinfunction "2_2") (pintype "passive"))
      (node (ref "S3") (pin "2") (pinfunction "P2_2") (pintype "bidirectional"))
      (node (ref "U1") (pin "10") (pinfunction "VBAT_10") (pintype "bidirectional"))
      (node (ref "U1") (pin "9") (pinfunction "VBAT_9") (pintype "bidirectional"))
    )
    (net (code "83") (name "VCCIO") (class "Default")
      (node (ref "LED5") (pin "A") (pinfunction "A_A") (pintype "passive"))
      (node (ref "LED6") (pin "A") (pinfunction "A_A") (pintype "passive"))
      (node (ref "U6") (pin "17") (pinfunction "3V3OUT_17") (pintype "output"))
      (node (ref "U6") (pin "4") (pinfunction "VCCIO_4") (pintype "power_in"))
    )
    (net (code "84") (name "VIN") (class "Default")
      (node (ref "C1") (pin "2") (pinfunction "2_2") (pintype "passive"))
      (node (ref "C9") (pin "1") (pinfunction "1_1") (pintype "passive"))
      (node (ref "L1") (pin "1") (pinfunction "1_1") (pintype "passive"))
      (node (ref "S3") (pin "1") (pinfunction "P1_1") (pintype "bidirectional"))
      (node (ref "U$3") (pin "P$4") (pinfunction "EN_P$4") (pintype "bidirectional"))
      (node (ref "U$3") (pin "P$6") (pinfunction "VIN_P$6") (pintype "bidirectional"))
      (node (ref "U$4") (pin "3") (pinfunction "IN_3") (pintype "input"))
    )
    (net (code "85") (name "XB_RST") (class "Default")
      (node (ref "R19") (pin "2") (pinfunction "2_2") (pintype "passive"))
      (node (ref "U$1") (pin "5") (pinfunction "RESET_5") (pintype "input"))
      (node (ref "U2") (pin "15") (pinfunction "P10_15") (pintype "bidirectional"))
    )
    (net (code "86") (name "XB_RX") (class "Default")
      (node (ref "U$1") (pin "3") (pinfunction "DIN_3") (pintype "input"))
      (node (ref "U2") (pin "14") (pinfunction "P9_14") (pintype "bidirectional"))
    )
    (net (code "87") (name "XB_TX") (class "Default")
      (node (ref "U$1") (pin "2") (pinfunction "DOUT_2") (pintype "output"))
      (node (ref "U2") (pin "13") (pinfunction "P8_13") (pintype "bidirectional"))
    )
    (net (code "88") (name "unconnected-(IC2A-A3-Pad6)") (class "Default")
      (node (ref "IC2") (pin "6") (pinfunction "A3_6") (pintype "input"))
    )
    (net (code "89") (name "unconnected-(IC2A-Y3-Pad14)") (class "Default")
      (node (ref "IC2") (pin "14") (pinfunction "Y3_14") (pintype "tri_state"))
    )
    (net (code "90") (name "unconnected-(J1-PAD1-PadNC1)") (class "Default")
      (node (ref "J1") (pin "NC1") (pinfunction "PAD1_NC1") (pintype "bidirectional"))
    )
    (net (code "91") (name "unconnected-(J1-PAD2-PadNC2)") (class "Default")
      (node (ref "J1") (pin "NC2") (pinfunction "PAD2_NC2") (pintype "bidirectional"))
    )
    (net (code "92") (name "unconnected-(J6-ID-PadP4)") (class "Default")
      (node (ref "J6") (pin "P4") (pinfunction "ID_P4") (pintype "bidirectional"))
    )
    (net (code "93") (name "unconnected-(J6-SH1-PadS1)") (class "Default")
      (node (ref "J6") (pin "S1") (pinfunction "SH1_S1") (pintype "passive"))
    )
    (net (code "94") (name "unconnected-(J6-SH2-PadS2)") (class "Default")
      (node (ref "J6") (pin "S2") (pinfunction "SH2_S2") (pintype "passive"))
    )
    (net (code "95") (name "unconnected-(J6-SH3-PadS3)") (class "Default")
      (node (ref "J6") (pin "S3") (pinfunction "SH3_S3") (pintype "passive"))
    )
    (net (code "96") (name "unconnected-(J6-SH4-PadS4)") (class "Default")
      (node (ref "J6") (pin "S4") (pinfunction "SH4_S4") (pintype "passive"))
    )
    (net (code "97") (name "unconnected-(J6-SH5-PadS5)") (class "Default")
      (node (ref "J6") (pin "S5") (pinfunction "SH5_S5") (pintype "passive"))
    )
    (net (code "98") (name "unconnected-(J6-SH6-PadS6)") (class "Default")
      (node (ref "J6") (pin "S6") (pinfunction "SH6_S6") (pintype "passive"))
    )
    (net (code "99") (name "unconnected-(S3-P3-Pad3)") (class "Default")
      (node (ref "S3") (pin "3") (pinfunction "P3_3") (pintype "bidirectional"))
    )
    (net (code "100") (name "unconnected-(U$1-CTS-Pad12)") (class "Default")
      (node (ref "U$1") (pin "12") (pinfunction "CTS_12") (pintype "output"))
    )
    (net (code "101") (name "unconnected-(U$1-DIO0-Pad20)") (class "Default")
      (node (ref "U$1") (pin "20") (pinfunction "DIO0_20") (pintype "bidirectional"))
    )
    (net (code "102") (name "unconnected-(U$1-DIO1-Pad19)") (class "Default")
      (node (ref "U$1") (pin "19") (pinfunction "DIO1_19") (pintype "bidirectional"))
    )
    (net (code "103") (name "unconnected-(U$1-DIO2-Pad18)") (class "Default")
      (node (ref "U$1") (pin "18") (pinfunction "DIO2_18") (pintype "bidirectional"))
    )
    (net (code "104") (name "unconnected-(U$1-DIO3-Pad17)") (class "Default")
      (node (ref "U$1") (pin "17") (pinfunction "DIO3_17") (pintype "bidirectional"))
    )
    (net (code "105") (name "unconnected-(U$1-DIO4-Pad11)") (class "Default")
      (node (ref "U$1") (pin "11") (pinfunction "DIO4_11") (pintype "bidirectional"))
    )
    (net (code "106") (name "unconnected-(U$1-DIO5-Pad15)") (class "Default")
      (node (ref "U$1") (pin "15") (pinfunction "DIO5_15") (pintype "bidirectional"))
    )
    (net (code "107") (name "unconnected-(U$1-DIO9-Pad13)") (class "Default")
      (node (ref "U$1") (pin "13") (pinfunction "DIO9_13") (pintype "bidirectional"))
    )
    (net (code "108") (name "unconnected-(U$1-DIO11-Pad7)") (class "Default")
      (node (ref "U$1") (pin "7") (pinfunction "DIO11_7") (pintype "bidirectional"))
    )
    (net (code "109") (name "unconnected-(U$1-DIO12-Pad4)") (class "Default")
      (node (ref "U$1") (pin "4") (pinfunction "DIO12_4") (pintype "bidirectional"))
    )
    (net (code "110") (name "unconnected-(U$1-DTR-Pad9)") (class "Default")
      (node (ref "U$1") (pin "9") (pinfunction "DTR_9") (pintype "bidirectional"))
    )
    (net (code "111") (name "unconnected-(U$1-RES-Pad8)") (class "Default")
      (node (ref "U$1") (pin "8") (pinfunction "RES_8") (pintype "bidirectional"))
    )
    (net (code "112") (name "unconnected-(U$1-RES-Pad14)") (class "Default")
      (node (ref "U$1") (pin "14") (pinfunction "RES_14") (pintype "bidirectional"))
    )
    (net (code "113") (name "unconnected-(U$1-RSSI-Pad6)") (class "Default")
      (node (ref "U$1") (pin "6") (pinfunction "RSSI_6") (pintype "bidirectional"))
    )
    (net (code "114") (name "unconnected-(U$1-RTS-Pad16)") (class "Default")
      (node (ref "U$1") (pin "16") (pinfunction "RTS_16") (pintype "input"))
    )
    (net (code "115") (name "unconnected-(U$2-ADC-Pad10)") (class "Default")
      (node (ref "U$2") (pin "10") (pinfunction "ADC_10") (pintype "bidirectional"))
    )
    (net (code "116") (name "unconnected-(U$2-GPIO0-Pad4)") (class "Default")
      (node (ref "U$2") (pin "4") (pinfunction "GPIO0_4") (pintype "bidirectional"))
    )
    (net (code "117") (name "unconnected-(U$2-GPIO2-Pad3)") (class "Default")
      (node (ref "U$2") (pin "3") (pinfunction "GPIO2_3") (pintype "bidirectional"))
    )
    (net (code "118") (name "unconnected-(U$2-GPIO4-Pad6)") (class "Default")
      (node (ref "U$2") (pin "6") (pinfunction "GPIO4_6") (pintype "bidirectional"))
    )
    (net (code "119") (name "unconnected-(U$2-GPIO5-Pad5)") (class "Default")
      (node (ref "U$2") (pin "5") (pinfunction "GPIO5_5") (pintype "bidirectional"))
    )
    (net (code "120") (name "unconnected-(U$2-GPIO12-Pad14)") (class "Default")
      (node (ref "U$2") (pin "14") (pinfunction "GPIO12_14") (pintype "bidirectional"))
    )
    (net (code "121") (name "unconnected-(U$2-GPIO13-Pad15)") (class "Default")
      (node (ref "U$2") (pin "15") (pinfunction "GPIO13_15") (pintype "bidirectional"))
    )
    (net (code "122") (name "unconnected-(U$2-GPIO14-Pad13)") (class "Default")
      (node (ref "U$2") (pin "13") (pinfunction "GPIO14_13") (pintype "bidirectional"))
    )
    (net (code "123") (name "unconnected-(U$2-GPIO16-Pad12)") (class "Default")
      (node (ref "U$2") (pin "12") (pinfunction "GPIO16_12") (pintype "bidirectional"))
    )
    (net (code "124") (name "unconnected-(U5-PadA5)") (class "Default")
      (node (ref "U5") (pin "A5") (pinfunction "A5_A5") (pintype "bidirectional"))
    )
    (net (code "125") (name "unconnected-(U5-PadAREF)") (class "Default")
      (node (ref "U5") (pin "AREF") (pinfunction "AREF_AREF") (pintype "bidirectional"))
    )
    (net (code "126") (name "unconnected-(U5-PadRES)") (class "Default")
      (node (ref "U5") (pin "RES") (pinfunction "RES_RES") (pintype "bidirectional"))
    )
    (net (code "127") (name "unconnected-(U5-PadRX)") (class "Default")
      (node (ref "U5") (pin "RX") (pinfunction "RX_RX") (pintype "bidirectional"))
    )
    (net (code "128") (name "unconnected-(U5-PadTX)") (class "Default")
      (node (ref "U5") (pin "TX") (pinfunction "TX_TX") (pintype "bidirectional"))
    )
    (net (code "129") (name "unconnected-(U5-PadVIN)") (class "Default")
      (node (ref "U5") (pin "VIN") (pinfunction "VIN_VIN") (pintype "bidirectional"))
    )
    (net (code "130") (name "unconnected-(U6-CTS-Pad11)") (class "Default")
      (node (ref "U6") (pin "11") (pinfunction "CTS_11") (pintype "input"))
    )
    (net (code "131") (name "unconnected-(U6-DCD-Pad10)") (class "Default")
      (node (ref "U6") (pin "10") (pinfunction "DCD_10") (pintype "input"))
    )
    (net (code "132") (name "unconnected-(U6-DSR-Pad9)") (class "Default")
      (node (ref "U6") (pin "9") (pinfunction "DSR_9") (pintype "input"))
    )
    (net (code "133") (name "unconnected-(U6-OSCI-Pad27)") (class "Default")
      (node (ref "U6") (pin "27") (pinfunction "OSCI_27") (pintype "input"))
    )
    (net (code "134") (name "unconnected-(U6-OSCO-Pad28)") (class "Default")
      (node (ref "U6") (pin "28") (pinfunction "OSCO_28") (pintype "output"))
    )
    (net (code "135") (name "unconnected-(U6-PWREN-Pad14)") (class "Default")
      (node (ref "U6") (pin "14") (pinfunction "PWREN_14") (pintype "input"))
    )
    (net (code "136") (name "unconnected-(U6-RI-Pad6)") (class "Default")
      (node (ref "U6") (pin "6") (pinfunction "RI_6") (pintype "input"))
    )
    (net (code "137") (name "unconnected-(U6-SLEEP-Pad12)") (class "Default")
      (node (ref "U6") (pin "12") (pinfunction "SLEEP_12") (pintype "input"))
    )
    (net (code "138") (name "unconnected-(U6-TXDEN-Pad13)") (class "Default")
      (node (ref "U6") (pin "13") (pinfunction "TXDEN_13") (pintype "input"))
    )
    (net (code "139") (name "unconnected-(U11-AREF-Pad20)") (class "Default")
      (node (ref "U11") (pin "20") (pinfunction "AREF_20") (pintype "bidirectional"))
    )
  )
)
